# NitroxAnalyzer_v_0_3.net
KiCad netlist of a schematic drawn in EAGLE
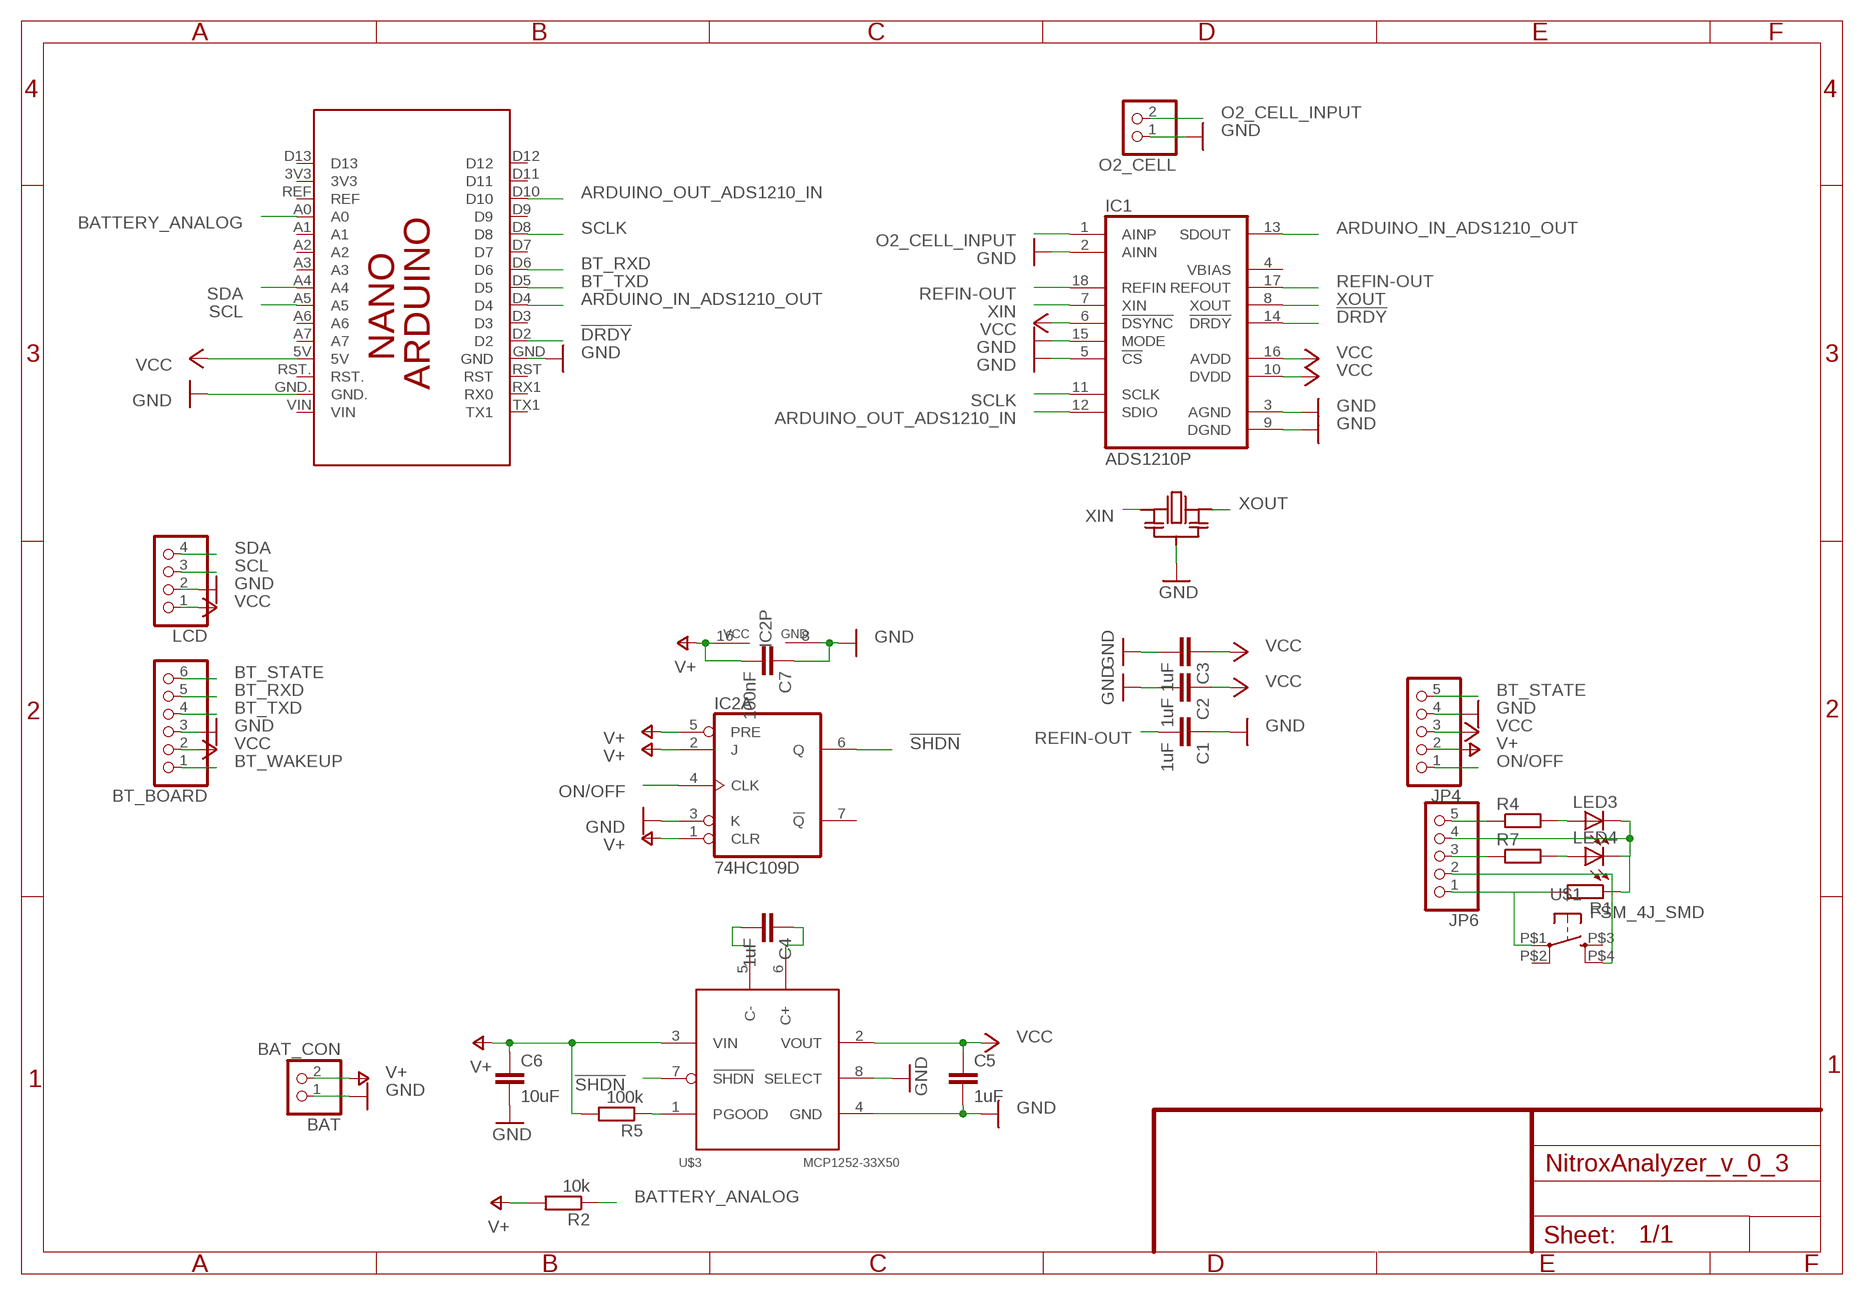
[diagram p0: schematic, sheet 1]

(export (version "E")
  (design (tool "Eeschema 10.0.6"))
  (components
    (comp (ref "BAT")
      (value "BAT_CON")
      (footprint "eagle-import:1X02")
      (libsource (lib "eagle-import") (part "PINHD-1X2"))
    )
    (comp (ref "BT_BOARD")
      (value "PINHD-1X6")
      (footprint "eagle-import:1X06")
      (libsource (lib "eagle-import") (part "PINHD-1X6"))
    )
    (comp (ref "C1")
      (value "1uF")
      (footprint "eagle-import:C1206")
      (libsource (lib "eagle-import") (part "C-EUC1206"))
    )
    (comp (ref "C2")
      (value "1uF")
      (footprint "eagle-import:C1206")
      (libsource (lib "eagle-import") (part "C-EUC1206"))
    )
    (comp (ref "C3")
      (value "1uF")
      (footprint "eagle-import:C1206")
      (libsource (lib "eagle-import") (part "C-EUC1206"))
    )
    (comp (ref "C4")
      (value "1uF")
      (footprint "eagle-import:C1206")
      (libsource (lib "eagle-import") (part "C-EUC1206"))
    )
    (comp (ref "C5")
      (value "1uF")
      (footprint "eagle-import:C1206")
      (libsource (lib "eagle-import") (part "C-EUC1206"))
    )
    (comp (ref "C6")
      (value "10uF")
      (footprint "eagle-import:C1206")
      (libsource (lib "eagle-import") (part "C-EUC1206"))
    )
    (comp (ref "C7")
      (value "100nF")
      (footprint "eagle-import:C1206")
      (libsource (lib "eagle-import") (part "C-EUC1206"))
    )
    (comp (ref "IC1")
      (value "ADS1210P")
      (footprint "eagle-import:DIL18")
      (libsource (lib "eagle-import") (part "ADS1210P"))
    )
    (comp (ref "IC2")
      (value "74HC109D")
      (footprint "eagle-import:SO16")
      (libsource (lib "eagle-import") (part "74109DHC"))
    )
    (comp (ref "JP4")
      (value "PINHD-1X5")
      (footprint "eagle-import:1X05")
      (libsource (lib "eagle-import") (part "PINHD-1X5"))
    )
    (comp (ref "JP6")
      (value "PINHD-1X5/90")
      (footprint "eagle-import:1X05_90")
      (libsource (lib "eagle-import") (part "PINHD-1X5/90"))
    )
    (comp (ref "LCD")
      (value "PINHD-1X4")
      (footprint "eagle-import:1X04")
      (libsource (lib "eagle-import") (part "PINHD-1X4"))
    )
    (comp (ref "LED3")
      (value "LEDSML0805")
      (footprint "eagle-import:SML0805")
      (libsource (lib "eagle-import") (part "LEDSML0805"))
    )
    (comp (ref "LED4")
      (value "LEDSML0805")
      (footprint "eagle-import:SML0805")
      (libsource (lib "eagle-import") (part "LEDSML0805"))
    )
    (comp (ref "O2_CELL")
      (value "PINHD-1X2")
      (footprint "eagle-import:1X02")
      (libsource (lib "eagle-import") (part "PINHD-1X2"))
    )
    (comp (ref "PCB1")
      (value "ARDUINO_NANO_SOCKET")
      (footprint "eagle-import:ARDUINO_NANO_SOCKET")
      (libsource (lib "eagle-import") (part "ARDUINO_NANO_SOCKET"))
    )
    (comp (ref "R1")
      (value "R-EU_R1206")
      (footprint "eagle-import:R1206")
      (libsource (lib "eagle-import") (part "R-EU_R1206"))
    )
    (comp (ref "R2")
      (value "10k")
      (footprint "eagle-import:R1206")
      (libsource (lib "eagle-import") (part "R-EU_R1206"))
    )
    (comp (ref "R4")
      (value "R-EU_R1206")
      (footprint "eagle-import:R1206")
      (libsource (lib "eagle-import") (part "R-EU_R1206"))
    )
    (comp (ref "R5")
      (value "100k")
      (footprint "eagle-import:R1206")
      (libsource (lib "eagle-import") (part "R-EU_R1206"))
    )
    (comp (ref "R7")
      (value "R-EU_R1206")
      (footprint "eagle-import:R1206")
      (libsource (lib "eagle-import") (part "R-EU_R1206"))
    )
    (comp (ref "U$1")
      (value "FSM_4J_SMD")
      (footprint "eagle-import:B3F-10XX")
      (libsource (lib "eagle-import") (part "FSM_4J_SMD"))
    )
    (comp (ref "U$2")
      (value "RESONATOR")
      (footprint "eagle-import:RESONATOR")
      (libsource (lib "eagle-import") (part "RESONATOR"))
    )
    (comp (ref "U$3")
      (value "MCP1252-33X50")
      (footprint "eagle-import:MSOP8")
      (libsource (lib "eagle-import") (part "MCP1252-33X50"))
    )
  )
  (nets
    (net (code "1") (name "/ARDUINO_IN_ADS1210_OUT") (class "Default")
      (node (ref "IC1") (pin "13") (pinfunction "SDOUT_13") (pintype "output"))
      (node (ref "PCB1") (pin "D4") (pinfunction "D4_D4") (pintype "bidirectional"))
    )
    (net (code "2") (name "/ARDUINO_OUT_ADS1210_IN") (class "Default")
      (node (ref "IC1") (pin "12") (pinfunction "SDIO_12") (pintype "bidirectional"))
      (node (ref "PCB1") (pin "D10") (pinfunction "D10_D10") (pintype "bidirectional"))
    )
    (net (code "3") (name "/BATTERY_ANALOG") (class "Default")
      (node (ref "PCB1") (pin "A0") (pinfunction "A0_A0") (pintype "bidirectional"))
      (node (ref "R2") (pin "1") (pinfunction "1_1") (pintype "passive"))
    )
    (net (code "4") (name "/BT_RXD") (class "Default")
      (node (ref "BT_BOARD") (pin "5") (pinfunction "5_5") (pintype "passive"))
      (node (ref "PCB1") (pin "D6") (pinfunction "D6_D6") (pintype "bidirectional"))
    )
    (net (code "5") (name "/BT_STATE") (class "Default")
      (node (ref "BT_BOARD") (pin "6") (pinfunction "6_6") (pintype "passive"))
      (node (ref "JP4") (pin "5") (pinfunction "5_5") (pintype "passive"))
    )
    (net (code "6") (name "/BT_TXD") (class "Default")
      (node (ref "BT_BOARD") (pin "4") (pinfunction "4_4") (pintype "passive"))
      (node (ref "PCB1") (pin "D5") (pinfunction "D5_D5") (pintype "bidirectional"))
    )
    (net (code "7") (name "/BT_WAKEUP") (class "Default")
      (node (ref "BT_BOARD") (pin "1") (pinfunction "1_1") (pintype "passive"))
    )
    (net (code "8") (name "/O2_CELL_INPUT") (class "Default")
      (node (ref "IC1") (pin "1") (pinfunction "AINP_1") (pintype "input"))
      (node (ref "O2_CELL") (pin "2") (pinfunction "2_2") (pintype "passive"))
    )
    (net (code "9") (name "/ON{slash}OFF") (class "Default")
      (node (ref "IC2") (pin "4") (pinfunction "CLK_4") (pintype "input"))
      (node (ref "JP4") (pin "1") (pinfunction "1_1") (pintype "passive"))
    )
    (net (code "10") (name "/REFIN-OUT") (class "Default")
      (node (ref "C1") (pin "2") (pinfunction "2_2") (pintype "passive"))
      (node (ref "IC1") (pin "17") (pinfunction "REFOUT_17") (pintype "output"))
      (node (ref "IC1") (pin "18") (pinfunction "REFIN_18") (pintype "input"))
    )
    (net (code "11") (name "/SCL") (class "Default")
      (node (ref "LCD") (pin "3") (pinfunction "3_3") (pintype "passive"))
      (node (ref "PCB1") (pin "A5") (pinfunction "A5_A5") (pintype "bidirectional"))
    )
    (net (code "12") (name "/SCLK") (class "Default")
      (node (ref "IC1") (pin "11") (pinfunction "SCLK_11") (pintype "bidirectional"))
      (node (ref "PCB1") (pin "D8") (pinfunction "D8_D8") (pintype "bidirectional"))
    )
    (net (code "13") (name "/SDA") (class "Default")
      (node (ref "LCD") (pin "4") (pinfunction "4_4") (pintype "passive"))
      (node (ref "PCB1") (pin "A4") (pinfunction "A4_A4") (pintype "bidirectional"))
    )
    (net (code "14") (name "/XIN") (class "Default")
      (node (ref "IC1") (pin "7") (pinfunction "XIN_7") (pintype "input"))
      (node (ref "U$2") (pin "P$1") (pinfunction "IN_P$1") (pintype "bidirectional"))
    )
    (net (code "15") (name "/XOUT") (class "Default")
      (node (ref "IC1") (pin "8") (pinfunction "XOUT_8") (pintype "output"))
      (node (ref "U$2") (pin "P$3") (pinfunction "OUT_P$3") (pintype "bidirectional"))
    )
    (net (code "16") (name "/~{DRDY}") (class "Default")
      (node (ref "IC1") (pin "14") (pinfunction "~{DRDY}_14") (pintype "output"))
      (node (ref "PCB1") (pin "D2") (pinfunction "D2_D2") (pintype "bidirectional"))
    )
    (net (code "17") (name "/~{SHDN}") (class "Default")
      (node (ref "IC2") (pin "6") (pinfunction "Q_6") (pintype "output"))
      (node (ref "U$3") (pin "7") (pinfunction "SHDN_7") (pintype "input"))
    )
    (net (code "18") (name "GND") (class "Default")
      (node (ref "BAT") (pin "1") (pinfunction "1_1") (pintype "passive"))
      (node (ref "BT_BOARD") (pin "3") (pinfunction "3_3") (pintype "passive"))
      (node (ref "C1") (pin "1") (pinfunction "1_1") (pintype "passive"))
      (node (ref "C2") (pin "2") (pinfunction "2_2") (pintype "passive"))
      (node (ref "C3") (pin "2") (pinfunction "2_2") (pintype "passive"))
      (node (ref "C5") (pin "2") (pinfunction "2_2") (pintype "passive"))
      (node (ref "C6") (pin "2") (pinfunction "2_2") (pintype "passive"))
      (node (ref "C7") (pin "1") (pinfunction "1_1") (pintype "passive"))
      (node (ref "IC1") (pin "15") (pinfunction "MODE_15") (pintype "input"))
      (node (ref "IC1") (pin "2") (pinfunction "AINN_2") (pintype "input"))
      (node (ref "IC1") (pin "3") (pinfunction "AGND_3") (pintype "power_in"))
      (node (ref "IC1") (pin "5") (pinfunction "~{CS}_5") (pintype "input"))
      (node (ref "IC1") (pin "9") (pinfunction "DGND_9") (pintype "power_in"))
      (node (ref "IC2") (pin "3") (pinfunction "K_3") (pintype "input"))
      (node (ref "IC2") (pin "8") (pinfunction "GND_8") (pintype "power_in"))
      (node (ref "JP4") (pin "4") (pinfunction "4_4") (pintype "passive"))
      (node (ref "LCD") (pin "2") (pinfunction "2_2") (pintype "passive"))
      (node (ref "O2_CELL") (pin "1") (pinfunction "1_1") (pintype "passive"))
      (node (ref "PCB1") (pin "GND") (pinfunction "GND_GND") (pintype "bidirectional"))
      (node (ref "PCB1") (pin "GND.") (pinfunction "GND._GND.") (pintype "bidirectional"))
      (node (ref "U$2") (pin "P$2") (pinfunction "GND_P$2") (pintype "bidirectional"))
      (node (ref "U$3") (pin "4") (pinfunction "GND_4") (pintype "power_in"))
      (node (ref "U$3") (pin "8") (pinfunction "SELECT_8") (pintype "input"))
    )
    (net (code "19") (name "Net-(JP6-Pad3)") (class "Default")
      (node (ref "JP6") (pin "3") (pinfunction "3_3") (pintype "passive"))
      (node (ref "R7") (pin "1") (pinfunction "1_1") (pintype "passive"))
    )
    (net (code "20") (name "Net-(JP6-Pad4)") (class "Default")
      (node (ref "JP6") (pin "4") (pinfunction "4_4") (pintype "passive"))
      (node (ref "LED3") (pin "C") (pinfunction "C_C") (pintype "passive"))
      (node (ref "LED4") (pin "C") (pinfunction "C_C") (pintype "passive"))
      (node (ref "R1") (pin "1") (pinfunction "1_1") (pintype "passive"))
    )
    (net (code "21") (name "Net-(JP6-Pad5)") (class "Default")
      (node (ref "JP6") (pin "5") (pinfunction "5_5") (pintype "passive"))
      (node (ref "R4") (pin "1") (pinfunction "1_1") (pintype "passive"))
    )
    (net (code "22") (name "Net-(LED3-PadA)") (class "Default")
      (node (ref "LED3") (pin "A") (pinfunction "A_A") (pintype "passive"))
      (node (ref "R4") (pin "2") (pinfunction "2_2") (pintype "passive"))
    )
    (net (code "23") (name "Net-(LED4-PadA)") (class "Default")
      (node (ref "LED4") (pin "A") (pinfunction "A_A") (pintype "passive"))
      (node (ref "R7") (pin "2") (pinfunction "2_2") (pintype "passive"))
    )
    (net (code "24") (name "Net-(U$1-P)") (class "Default")
      (node (ref "JP6") (pin "1") (pinfunction "1_1") (pintype "passive"))
      (node (ref "R1") (pin "2") (pinfunction "2_2") (pintype "passive"))
      (node (ref "U$1") (pin "P$1") (pinfunction "P_P$1") (pintype "passive"))
    )
    (net (code "25") (name "Net-(U$1-S1)") (class "Default")
      (node (ref "JP6") (pin "2") (pinfunction "2_2") (pintype "passive"))
      (node (ref "U$1") (pin "P$4") (pinfunction "S1_P$4") (pintype "passive"))
    )
    (net (code "26") (name "Net-(U$3-C+)") (class "Default")
      (node (ref "C4") (pin "1") (pinfunction "1_1") (pintype "passive"))
      (node (ref "U$3") (pin "6") (pinfunction "C+_6") (pintype "bidirectional"))
    )
    (net (code "27") (name "Net-(U$3-C-)") (class "Default")
      (node (ref "C4") (pin "2") (pinfunction "2_2") (pintype "passive"))
      (node (ref "U$3") (pin "5") (pinfunction "C-_5") (pintype "bidirectional"))
    )
    (net (code "28") (name "Net-(U$3-PGOOD)") (class "Default")
      (node (ref "R5") (pin "1") (pinfunction "1_1") (pintype "passive"))
      (node (ref "U$3") (pin "1") (pinfunction "PGOOD_1") (pintype "output"))
    )
    (net (code "29") (name "V+") (class "Default")
      (node (ref "BAT") (pin "2") (pinfunction "2_2") (pintype "passive"))
      (node (ref "C6") (pin "1") (pinfunction "1_1") (pintype "passive"))
      (node (ref "C7") (pin "2") (pinfunction "2_2") (pintype "passive"))
      (node (ref "IC2") (pin "1") (pinfunction "CLR_1") (pintype "input"))
      (node (ref "IC2") (pin "16") (pinfunction "VCC_16") (pintype "power_in"))
      (node (ref "IC2") (pin "2") (pinfunction "J_2") (pintype "input"))
      (node (ref "IC2") (pin "5") (pinfunction "PRE_5") (pintype "input"))
      (node (ref "JP4") (pin "2") (pinfunction "2_2") (pintype "passive"))
      (node (ref "R2") (pin "2") (pinfunction "2_2") (pintype "passive"))
      (node (ref "R5") (pin "2") (pinfunction "2_2") (pintype "passive"))
      (node (ref "U$3") (pin "3") (pinfunction "VIN_3") (pintype "power_in"))
    )
    (net (code "30") (name "VCC") (class "Default")
      (node (ref "BT_BOARD") (pin "2") (pinfunction "2_2") (pintype "passive"))
      (node (ref "C2") (pin "1") (pinfunction "1_1") (pintype "passive"))
      (node (ref "C3") (pin "1") (pinfunction "1_1") (pintype "passive"))
      (node (ref "C5") (pin "1") (pinfunction "1_1") (pintype "passive"))
      (node (ref "IC1") (pin "10") (pinfunction "DVDD_10") (pintype "power_in"))
      (node (ref "IC1") (pin "16") (pinfunction "AVDD_16") (pintype "power_in"))
      (node (ref "IC1") (pin "6") (pinfunction "~{DSYNC}_6") (pintype "input"))
      (node (ref "JP4") (pin "3") (pinfunction "3_3") (pintype "passive"))
      (node (ref "LCD") (pin "1") (pinfunction "1_1") (pintype "passive"))
      (node (ref "PCB1") (pin "5V") (pinfunction "5V_5V") (pintype "bidirectional"))
      (node (ref "U$3") (pin "2") (pinfunction "VOUT_2") (pintype "output"))
    )
    (net (code "31") (name "unconnected-(IC1-VBIAS-Pad4)") (class "Default")
      (node (ref "IC1") (pin "4") (pinfunction "VBIAS_4") (pintype "output"))
    )
    (net (code "32") (name "unconnected-(IC2A-~{Q}-Pad7)") (class "Default")
      (node (ref "IC2") (pin "7") (pinfunction "~{Q}_7") (pintype "output"))
    )
    (net (code "33") (name "unconnected-(PCB1-Pad3V3)") (class "Default")
      (node (ref "PCB1") (pin "3V3") (pinfunction "3V3_3V3") (pintype "bidirectional"))
    )
    (net (code "34") (name "unconnected-(PCB1-PadA1)") (class "Default")
      (node (ref "PCB1") (pin "A1") (pinfunction "A1_A1") (pintype "bidirectional"))
    )
    (net (code "35") (name "unconnected-(PCB1-PadA2)") (class "Default")
      (node (ref "PCB1") (pin "A2") (pinfunction "A2_A2") (pintype "bidirectional"))
    )
    (net (code "36") (name "unconnected-(PCB1-PadA3)") (class "Default")
      (node (ref "PCB1") (pin "A3") (pinfunction "A3_A3") (pintype "bidirectional"))
    )
    (net (code "37") (name "unconnected-(PCB1-PadA6)") (class "Default")
      (node (ref "PCB1") (pin "A6") (pinfunction "A6_A6") (pintype "bidirectional"))
    )
    (net (code "38") (name "unconnected-(PCB1-PadA7)") (class "Default")
      (node (ref "PCB1") (pin "A7") (pinfunction "A7_A7") (pintype "bidirectional"))
    )
    (net (code "39") (name "unconnected-(PCB1-PadD3)") (class "Default")
      (node (ref "PCB1") (pin "D3") (pinfunction "D3_D3") (pintype "bidirectional"))
    )
    (net (code "40") (name "unconnected-(PCB1-PadD7)") (class "Default")
      (node (ref "PCB1") (pin "D7") (pinfunction "D7_D7") (pintype "bidirectional"))
    )
    (net (code "41") (name "unconnected-(PCB1-PadD9)") (class "Default")
      (node (ref "PCB1") (pin "D9") (pinfunction "D9_D9") (pintype "bidirectional"))
    )
    (net (code "42") (name "unconnected-(PCB1-PadD11)") (class "Default")
      (node (ref "PCB1") (pin "D11") (pinfunction "D11_D11") (pintype "bidirectional"))
    )
    (net (code "43") (name "unconnected-(PCB1-PadD12)") (class "Default")
      (node (ref "PCB1") (pin "D12") (pinfunction "D12_D12") (pintype "bidirectional"))
    )
    (net (code "44") (name "unconnected-(PCB1-PadD13)") (class "Default")
      (node (ref "PCB1") (pin "D13") (pinfunction "D13_D13") (pintype "bidirectional"))
    )
    (net (code "45") (name "unconnected-(PCB1-PadREF)") (class "Default")
      (node (ref "PCB1") (pin "REF") (pinfunction "REF_REF") (pintype "bidirectional"))
    )
    (net (code "46") (name "unconnected-(PCB1-PadRST)") (class "Default")
      (node (ref "PCB1") (pin "RST") (pinfunction "RST_RST") (pintype "bidirectional"))
    )
    (net (code "47") (name "unconnected-(PCB1-PadRST.)") (class "Default")
      (node (ref "PCB1") (pin "RST.") (pinfunction "RST._RST.") (pintype "bidirectional"))
    )
    (net (code "48") (name "unconnected-(PCB1-PadTX1)") (class "Default")
      (node (ref "PCB1") (pin "TX1") (pinfunction "TX1_TX1") (pintype "bidirectional"))
    )
    (net (code "49") (name "unconnected-(PCB1-PadVIN)") (class "Default")
      (node (ref "PCB1") (pin "VIN") (pinfunction "VIN_VIN") (pintype "bidirectional"))
    )
    (net (code "50") (name "unconnected-(PCB1-RX0-PadRX1)") (class "Default")
      (node (ref "PCB1") (pin "RX1") (pinfunction "RX0_RX1") (pintype "bidirectional"))
    )
    (net (code "51") (name "unconnected-(U$1-P1-PadP$2)") (class "Default")
      (node (ref "U$1") (pin "P$2") (pinfunction "P1_P$2") (pintype "passive"))
    )
    (net (code "52") (name "unconnected-(U$1-S-PadP$3)") (class "Default")
      (node (ref "U$1") (pin "P$3") (pinfunction "S_P$3") (pintype "passive"))
    )
  )
)
